# ipg_wearable.net
KiCad netlist of a schematic drawn in Altium Designer
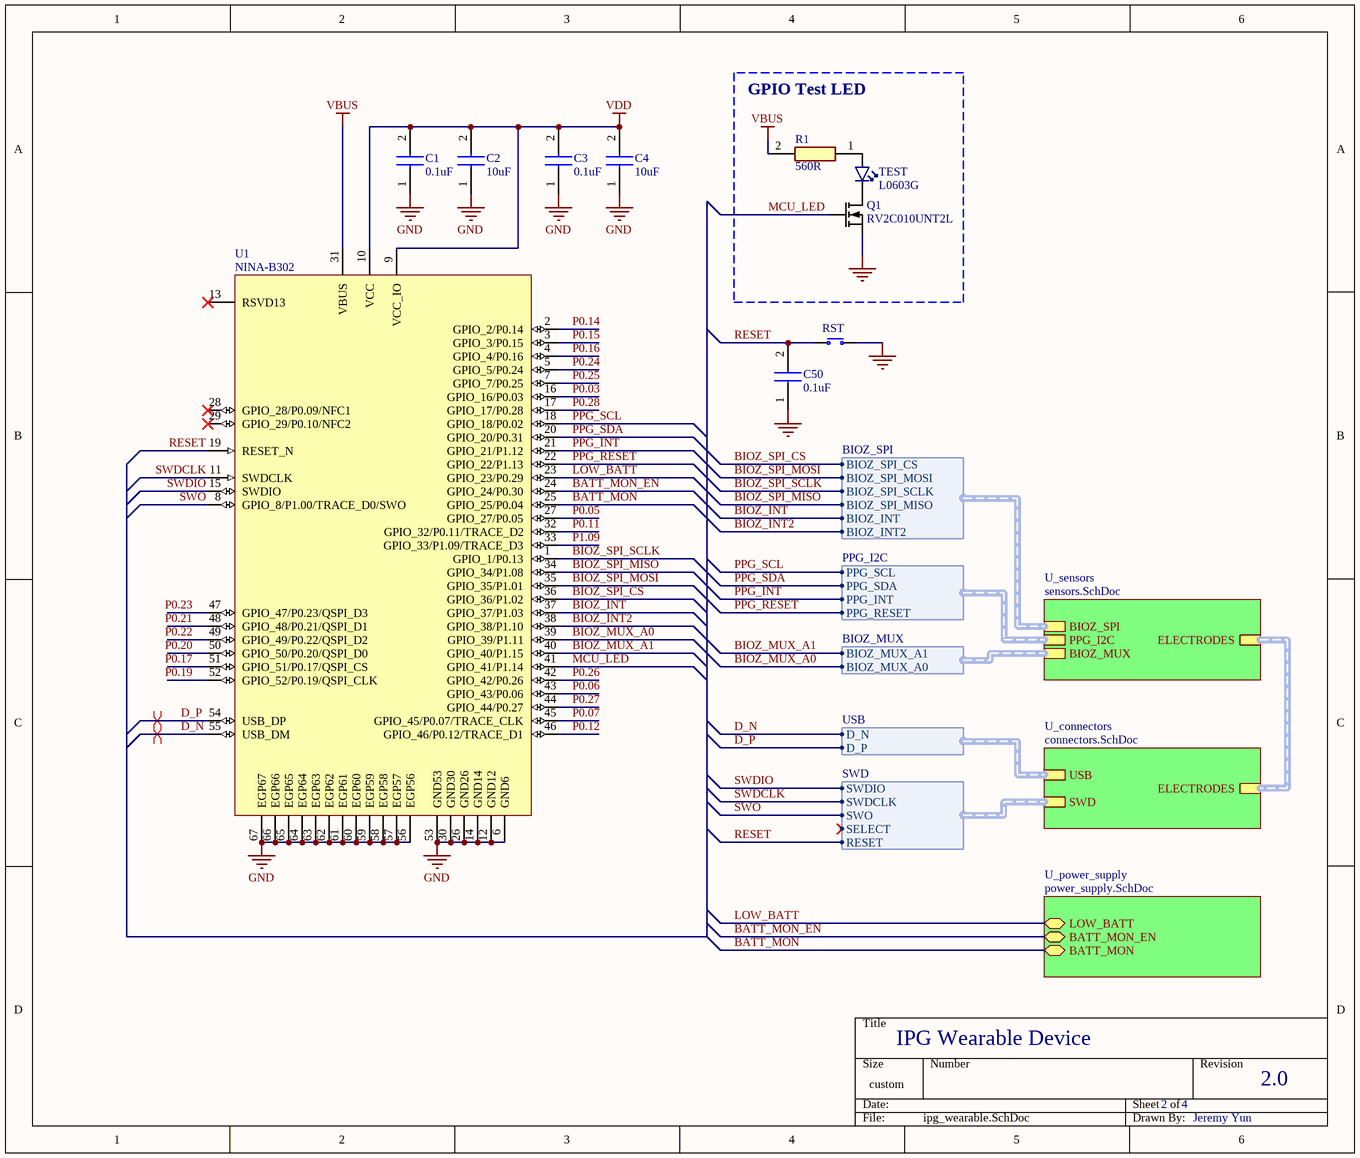
[diagram p0: ipg_wearable.SchDoc]

(export (version "E")
  (design (tool "Eeschema 10.0.6"))
  (components
    (comp (ref "C1")
      (value "0.1uF")
      (footprint "CAPC1005X55N")
      (description "Capacitor")
      (fields (field (name "MANUFACTURER_PART_NUMBER") "GRM155R71C104KA88D"))
      (libsource (lib "V2_wearable") (part "GRM155R71C104KA88D"))
    )
    (comp (ref "C2")
      (value "10uF")
      (footprint "V2_wearable:CAPC1005X55N")
      (description "Capacitor 10uF X5R Ceramic")
      (fields
        (field (name "MANUFACTURER_PART_NUMBER") "GRM155R60J106ME05D")
        (field (name "MOUSER PART NUMBER") "81-GRM155R60J106M05D")
      )
      (libsource (lib "*") (part "GRM155R60J106ME05D"))
    )
    (comp (ref "C3")
      (value "0.1uF")
      (footprint "CAPC1005X55N")
      (description "Capacitor")
      (fields (field (name "MANUFACTURER_PART_NUMBER") "GRM155R71C104KA88D"))
      (libsource (lib "V2_wearable") (part "GRM155R71C104KA88D"))
    )
    (comp (ref "C4")
      (value "10uF")
      (footprint "V2_wearable:CAPC1005X55N")
      (description "Capacitor 10uF X5R Ceramic")
      (fields
        (field (name "MANUFACTURER_PART_NUMBER") "GRM155R60J106ME05D")
        (field (name "MOUSER PART NUMBER") "81-GRM155R60J106M05D")
      )
      (libsource (lib "*") (part "GRM155R60J106ME05D"))
    )
    (comp (ref "C50")
      (value "0.1uF")
      (footprint "CAPC1005X55N")
      (description "Capacitor")
      (fields (field (name "MANUFACTURER_PART_NUMBER") "GRM155R71C104KA88D"))
      (libsource (lib "V2_wearable") (part "GRM155R71C104KA88D"))
    )
    (comp (ref "Q1")
      (value "RV2C010UNT2L")
      (footprint "DFN65P100X40-3L")
      (description "N-Channel MOSFET, 20V, 1A, 470mOhm, 400mW")
      (fields (field (name "MANUFACTURER") "Rohm Semiconductor") (field (name "AUTHOR") "rsk"))
      (libsource (lib "V2_wearable") (part "RV2C010UNT2L"))
    )
    (comp (ref "R1")
      (value "560R")
      (footprint "RESC1005X40N")
      (description "Resistor")
      (fields
        (field (name "MANUFACTURER_PART_NUMBER") "RC0402JR-07560RL")
        (field (name "MOUSER PART NUMBER") "603-RC0402JR-07560RL")
      )
      (libsource (lib "V2_wearable") (part "RC0402JR-07560RL"))
    )
    (comp (ref "RST")
      (value "TL1017AABF160QG")
      (footprint "V2_wearable:TL1017AABF160QG")
      (description "Tactile Push Button Switch")
      (fields (field (name "MOUSER PART NUMBER") "612-TL1017AABF160QG"))
      (libsource (lib "V2_wearable") (part "TL1017AABF160QG"))
    )
    (comp (ref "TEST")
      (value "L0603G")
      (footprint "LED_0603_G")
      (description "LED, Green, 0603, 573nm, Vf=2.0V, 24mcd, - 40 to +85°C")
      (fields
        (field (name "PART NUMBER") "VS 25C7M5")
        (field (name "MANUFACTURER") "Victory Electronics")
        (field (name "AUTHOR") "rsk")
      )
      (libsource (lib "V2_wearable") (part "VS 25C7M5"))
    )
    (comp (ref "U1")
      (value "NINA-B302")
      (footprint "V2_wearable:NINA_LGA67R_1500X1000X338_PIFA")
      (description "u-blox NINA-B302 Bluetooth 5 LE, 802.15.4 module")
      (fields (field (name "MANUFACTURER") "u-blox"))
      (libsource (lib "V2_wearable") (part "NINA-B302"))
    )
  )
  (nets
    (net (code "6") (name "/BATT_MON") (class "Default")
      (node (ref "U1") (pin "25") (pinfunction "GPIO_25/P0.04_25") (pintype "bidirectional"))
    )
    (net (code "7") (name "/BATT_MON_EN") (class "Default")
      (node (ref "U1") (pin "24") (pinfunction "GPIO_24/P0.30_24") (pintype "bidirectional"))
    )
    (net (code "8") (name "/BIOZ_INT") (class "Default")
      (node (ref "U1") (pin "37") (pinfunction "GPIO_37/P1.03_37") (pintype "bidirectional"))
    )
    (net (code "9") (name "/BIOZ_INT2") (class "Default")
      (node (ref "U1") (pin "38") (pinfunction "GPIO_38/P1.10_38") (pintype "bidirectional"))
    )
    (net (code "10") (name "/BIOZ_MUX_A0") (class "Default")
      (node (ref "U1") (pin "39") (pinfunction "GPIO_39/P1.11_39") (pintype "bidirectional"))
    )
    (net (code "11") (name "/BIOZ_MUX_A1") (class "Default")
      (node (ref "U1") (pin "40") (pinfunction "GPIO_40/P1.15_40") (pintype "bidirectional"))
    )
    (net (code "12") (name "/BIOZ_SPI_CS") (class "Default")
      (node (ref "U1") (pin "36") (pinfunction "GPIO_36/P1.02_36") (pintype "bidirectional"))
    )
    (net (code "13") (name "/BIOZ_SPI_MISO") (class "Default")
      (node (ref "U1") (pin "34") (pinfunction "GPIO_34/P1.08_34") (pintype "bidirectional"))
    )
    (net (code "14") (name "/BIOZ_SPI_MOSI") (class "Default")
      (node (ref "U1") (pin "35") (pinfunction "GPIO_35/P1.01_35") (pintype "bidirectional"))
    )
    (net (code "15") (name "/BIOZ_SPI_SCLK") (class "Default")
      (node (ref "U1") (pin "1") (pinfunction "GPIO_1/P0.13_1") (pintype "bidirectional"))
    )
    (net (code "16") (name "/D_N") (class "Default")
      (node (ref "U1") (pin "55") (pinfunction "USB_DM_55") (pintype "bidirectional"))
    )
    (net (code "17") (name "/D_P") (class "Default")
      (node (ref "U1") (pin "54") (pinfunction "USB_DP_54") (pintype "bidirectional"))
    )
    (net (code "19") (name "/LOW_BATT") (class "Default")
      (node (ref "U1") (pin "23") (pinfunction "GPIO_23/P0.29_23") (pintype "bidirectional"))
    )
    (net (code "20") (name "/MCU_LED") (class "Default")
      (node (ref "Q1") (pin "1") (pinfunction "G_1") (pintype "passive"))
      (node (ref "U1") (pin "41") (pinfunction "GPIO_41/P1.14_41") (pintype "bidirectional"))
    )
    (net (code "21") (name "/P0.03") (class "Default")
      (node (ref "U1") (pin "16") (pinfunction "GPIO_16/P0.03_16") (pintype "bidirectional"))
    )
    (net (code "22") (name "/P0.05") (class "Default")
      (node (ref "U1") (pin "27") (pinfunction "GPIO_27/P0.05_27") (pintype "bidirectional"))
    )
    (net (code "23") (name "/P0.06") (class "Default")
      (node (ref "U1") (pin "43") (pinfunction "GPIO_43/P0.06_43") (pintype "bidirectional"))
    )
    (net (code "24") (name "/P0.07") (class "Default")
      (node (ref "U1") (pin "45") (pinfunction "GPIO_45/P0.07/TRACE_CLK_45") (pintype "bidirectional"))
    )
    (net (code "25") (name "/P0.11") (class "Default")
      (node (ref "U1") (pin "32") (pinfunction "GPIO_32/P0.11/TRACE_D2_32") (pintype "bidirectional"))
    )
    (net (code "26") (name "/P0.12") (class "Default")
      (node (ref "U1") (pin "46") (pinfunction "GPIO_46/P0.12/TRACE_D1_46") (pintype "bidirectional"))
    )
    (net (code "27") (name "/P0.14") (class "Default")
      (node (ref "U1") (pin "2") (pinfunction "GPIO_2/P0.14_2") (pintype "bidirectional"))
    )
    (net (code "28") (name "/P0.15") (class "Default")
      (node (ref "U1") (pin "3") (pinfunction "GPIO_3/P0.15_3") (pintype "bidirectional"))
    )
    (net (code "29") (name "/P0.16") (class "Default")
      (node (ref "U1") (pin "4") (pinfunction "GPIO_4/P0.16_4") (pintype "bidirectional"))
    )
    (net (code "30") (name "/P0.17") (class "Default")
      (node (ref "U1") (pin "51") (pinfunction "GPIO_51/P0.17/QSPI_CS_51") (pintype "bidirectional"))
    )
    (net (code "31") (name "/P0.19") (class "Default")
      (node (ref "U1") (pin "52") (pinfunction "GPIO_52/P0.19/QSPI_CLK_52") (pintype "bidirectional"))
    )
    (net (code "32") (name "/P0.20") (class "Default")
      (node (ref "U1") (pin "50") (pinfunction "GPIO_50/P0.20/QSPI_D0_50") (pintype "bidirectional"))
    )
    (net (code "33") (name "/P0.21") (class "Default")
      (node (ref "U1") (pin "48") (pinfunction "GPIO_48/P0.21/QSPI_D1_48") (pintype "bidirectional"))
    )
    (net (code "34") (name "/P0.22") (class "Default")
      (node (ref "U1") (pin "49") (pinfunction "GPIO_49/P0.22/QSPI_D2_49") (pintype "bidirectional"))
    )
    (net (code "35") (name "/P0.23") (class "Default")
      (node (ref "U1") (pin "47") (pinfunction "GPIO_47/P0.23/QSPI_D3_47") (pintype "bidirectional"))
    )
    (net (code "36") (name "/P0.24") (class "Default")
      (node (ref "U1") (pin "5") (pinfunction "GPIO_5/P0.24_5") (pintype "bidirectional"))
    )
    (net (code "37") (name "/P0.25") (class "Default")
      (node (ref "U1") (pin "7") (pinfunction "GPIO_7/P0.25_7") (pintype "bidirectional"))
    )
    (net (code "38") (name "/P0.26") (class "Default")
      (node (ref "U1") (pin "42") (pinfunction "GPIO_42/P0.26_42") (pintype "bidirectional"))
    )
    (net (code "39") (name "/P0.27") (class "Default")
      (node (ref "U1") (pin "44") (pinfunction "GPIO_44/P0.27_44") (pintype "bidirectional"))
    )
    (net (code "40") (name "/P0.28") (class "Default")
      (node (ref "U1") (pin "17") (pinfunction "GPIO_17/P0.28_17") (pintype "bidirectional"))
    )
    (net (code "41") (name "/P1.09") (class "Default")
      (node (ref "U1") (pin "33") (pinfunction "GPIO_33/P1.09/TRACE_D3_33") (pintype "bidirectional"))
    )
    (net (code "42") (name "/PPG_INT") (class "Default")
      (node (ref "U1") (pin "21") (pinfunction "GPIO_21/P1.12_21") (pintype "bidirectional"))
    )
    (net (code "43") (name "/PPG_RESET") (class "Default")
      (node (ref "U1") (pin "22") (pinfunction "GPIO_22/P1.13_22") (pintype "bidirectional"))
    )
    (net (code "44") (name "/PPG_SCL") (class "Default")
      (node (ref "U1") (pin "18") (pinfunction "GPIO_18/P0.02_18") (pintype "bidirectional"))
    )
    (net (code "45") (name "/PPG_SDA") (class "Default")
      (node (ref "U1") (pin "20") (pinfunction "GPIO_20/P0.31_20") (pintype "bidirectional"))
    )
    (net (code "46") (name "/RESET") (class "Default")
      (node (ref "C50") (pin "2") (pinfunction "2_2") (pintype "passive"))
      (node (ref "RST") (pin "2") (pinfunction "COM_2") (pintype "passive"))
      (node (ref "U1") (pin "19") (pinfunction "RESET_N_19") (pintype "input"))
    )
    (net (code "47") (name "/SWDCLK") (class "Default")
      (node (ref "U1") (pin "11") (pinfunction "SWDCLK_11") (pintype "input"))
    )
    (net (code "48") (name "/SWDIO") (class "Default")
      (node (ref "U1") (pin "15") (pinfunction "SWDIO_15") (pintype "bidirectional"))
    )
    (net (code "49") (name "/SWO") (class "Default")
      (node (ref "U1") (pin "8") (pinfunction "GPIO_8/P1.00/TRACE_D0/SWO_8") (pintype "bidirectional"))
    )
    (net (code "55") (name "GND") (class "Default")
      (node (ref "C1") (pin "1") (pinfunction "1_1") (pintype "passive"))
      (node (ref "C2") (pin "1") (pinfunction "1_1") (pintype "passive"))
      (node (ref "C3") (pin "1") (pinfunction "1_1") (pintype "passive"))
      (node (ref "C4") (pin "1") (pinfunction "1_1") (pintype "passive"))
      (node (ref "C50") (pin "1") (pinfunction "1_1") (pintype "passive"))
      (node (ref "Q1") (pin "2") (pinfunction "S_2") (pintype "passive"))
      (node (ref "RST") (pin "1") (pinfunction "N.O_1") (pintype "passive"))
      (node (ref "U1") (pin "12") (pinfunction "GND12_12") (pintype "power_in"))
      (node (ref "U1") (pin "14") (pinfunction "GND14_14") (pintype "power_in"))
      (node (ref "U1") (pin "26") (pinfunction "GND26_26") (pintype "power_in"))
      (node (ref "U1") (pin "30") (pinfunction "GND30_30") (pintype "power_in"))
      (node (ref "U1") (pin "53") (pinfunction "GND53_53") (pintype "power_in"))
      (node (ref "U1") (pin "56") (pinfunction "EGP56_56") (pintype "power_in"))
      (node (ref "U1") (pin "57") (pinfunction "EGP57_57") (pintype "power_in"))
      (node (ref "U1") (pin "58") (pinfunction "EGP58_58") (pintype "power_in"))
      (node (ref "U1") (pin "59") (pinfunction "EGP59_59") (pintype "power_in"))
      (node (ref "U1") (pin "6") (pinfunction "GND6_6") (pintype "power_in"))
      (node (ref "U1") (pin "60") (pinfunction "EGP60_60") (pintype "power_in"))
      (node (ref "U1") (pin "61") (pinfunction "EGP61_61") (pintype "power_in"))
      (node (ref "U1") (pin "62") (pinfunction "EGP62_62") (pintype "power_in"))
      (node (ref "U1") (pin "63") (pinfunction "EGP63_63") (pintype "power_in"))
      (node (ref "U1") (pin "64") (pinfunction "EGP64_64") (pintype "power_in"))
      (node (ref "U1") (pin "65") (pinfunction "EGP65_65") (pintype "power_in"))
      (node (ref "U1") (pin "66") (pinfunction "EGP66_66") (pintype "power_in"))
      (node (ref "U1") (pin "67") (pinfunction "EGP67_67") (pintype "power_in"))
    )
    (net (code "56") (name "Net-(Q1-D)") (class "Default")
      (node (ref "Q1") (pin "3") (pinfunction "D_3") (pintype "passive"))
      (node (ref "TEST") (pin "1") (pinfunction "C_1") (pintype "passive"))
    )
    (net (code "57") (name "Net-(TEST-A)") (class "Default")
      (node (ref "R1") (pin "1") (pinfunction "1_1") (pintype "passive"))
      (node (ref "TEST") (pin "2") (pinfunction "A_2") (pintype "passive"))
    )
    (net (code "58") (name "VBUS") (class "Default")
      (node (ref "R1") (pin "2") (pinfunction "2_2") (pintype "passive"))
      (node (ref "U1") (pin "31") (pinfunction "VBUS_31") (pintype "power_in"))
    )
    (net (code "59") (name "VDD") (class "Default")
      (node (ref "C1") (pin "2") (pinfunction "2_2") (pintype "passive"))
      (node (ref "C2") (pin "2") (pinfunction "2_2") (pintype "passive"))
      (node (ref "C3") (pin "2") (pinfunction "2_2") (pintype "passive"))
      (node (ref "C4") (pin "2") (pinfunction "2_2") (pintype "passive"))
      (node (ref "U1") (pin "10") (pinfunction "VCC_10") (pintype "power_in"))
      (node (ref "U1") (pin "9") (pinfunction "VCC_IO_9") (pintype "power_in"))
    )
    (net (code "60") (name "unconnected-(U1-GPIO_28{slash}P0.09{slash}NFC1-Pad28)") (class "Default")
      (node (ref "U1") (pin "28") (pinfunction "GPIO_28/P0.09/NFC1_28") (pintype "bidirectional+no_connect"))
    )
    (net (code "61") (name "unconnected-(U1-GPIO_29{slash}P0.10{slash}NFC2-Pad29)") (class "Default")
      (node (ref "U1") (pin "29") (pinfunction "GPIO_29/P0.10/NFC2_29") (pintype "bidirectional+no_connect"))
    )
    (net (code "62") (name "unconnected-(U1-RSVD13-Pad13)") (class "Default")
      (node (ref "U1") (pin "13") (pinfunction "RSVD13_13") (pintype "passive+no_connect"))
    )
  )
)
